# hardware.net
KiCad netlist of a schematic drawn in Altium Designer
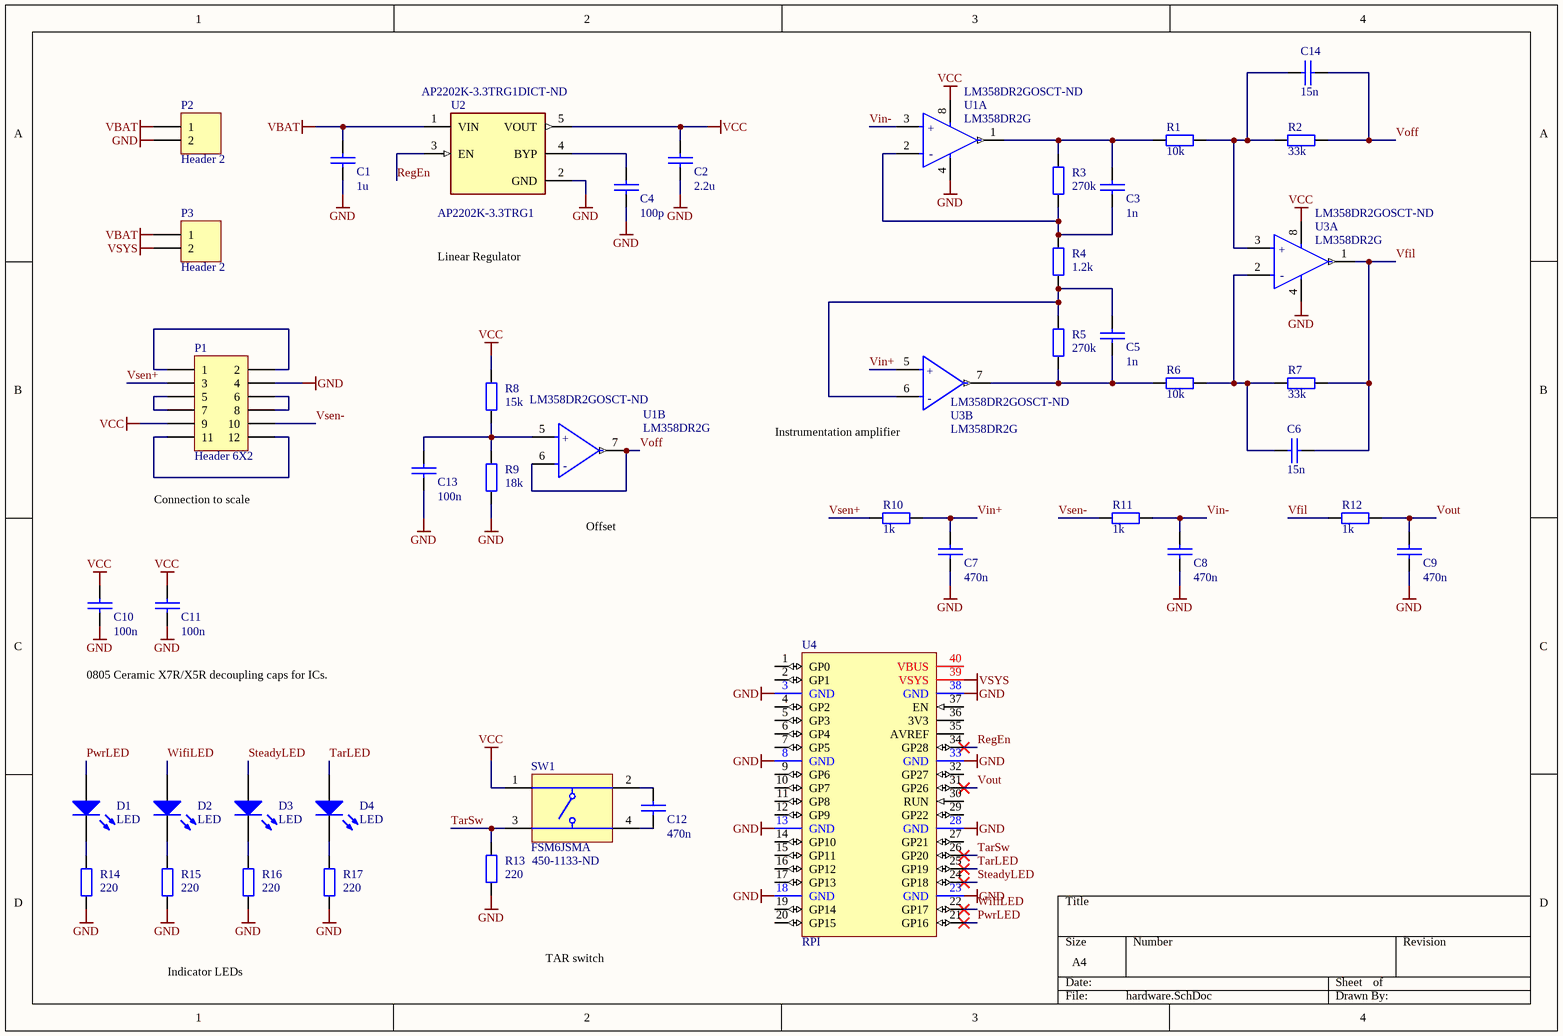
[diagram p0: hardware.SchDoc]

(export (version "E")
  (design (tool "Eeschema 10.0.6"))
  (components
    (comp (ref "C1")
      (value "1u")
      (footprint "EE311_footprints:C0805")
      (description "CCAP0805")
      (libsource (lib "EE311_symbols") (part "CCAP0805"))
    )
    (comp (ref "C2")
      (value "2.2u")
      (footprint "EE311_footprints:C0805")
      (description "CCAP0805")
      (libsource (lib "EE311_symbols") (part "CCAP0805"))
    )
    (comp (ref "C3")
      (value "1n")
      (footprint "EE311_footprints:C0805")
      (description "CCAP0805")
      (libsource (lib "EE311_symbols") (part "CCAP0805"))
    )
    (comp (ref "C4")
      (value "100p")
      (footprint "EE311_footprints:C0805")
      (description "CCAP0805")
      (libsource (lib "EE311_symbols") (part "CCAP0805"))
    )
    (comp (ref "C5")
      (value "1n")
      (footprint "EE311_footprints:C0805")
      (description "CCAP0805")
      (libsource (lib "EE311_symbols") (part "CCAP0805"))
    )
    (comp (ref "C6")
      (value "15n")
      (footprint "EE311_footprints:C0805")
      (description "CCAP0805")
      (libsource (lib "EE311_symbols") (part "CCAP0805"))
    )
    (comp (ref "C7")
      (value "470n")
      (footprint "EE311_footprints:C0805")
      (description "CCAP0805")
      (libsource (lib "EE311_symbols") (part "CCAP0805"))
    )
    (comp (ref "C8")
      (value "470n")
      (footprint "EE311_footprints:C0805")
      (description "CCAP0805")
      (libsource (lib "EE311_symbols") (part "CCAP0805"))
    )
    (comp (ref "C9")
      (value "470n")
      (footprint "EE311_footprints:C0805")
      (description "CCAP0805")
      (libsource (lib "EE311_symbols") (part "CCAP0805"))
    )
    (comp (ref "C10")
      (value "100n")
      (footprint "EE311_footprints:C0805")
      (description "CCAP0805")
      (libsource (lib "EE311_symbols") (part "CCAP0805"))
    )
    (comp (ref "C11")
      (value "100n")
      (footprint "EE311_footprints:C0805")
      (description "CCAP0805")
      (libsource (lib "EE311_symbols") (part "CCAP0805"))
    )
    (comp (ref "C12")
      (value "470n")
      (footprint "EE311_footprints:C0805")
      (description "CCAP0805")
      (libsource (lib "EE311_symbols") (part "CCAP0805"))
    )
    (comp (ref "C13")
      (value "100n")
      (footprint "EE311_footprints:C0805")
      (description "CCAP0805")
      (libsource (lib "EE311_symbols") (part "CCAP0805"))
    )
    (comp (ref "C14")
      (value "15n")
      (footprint "EE311_footprints:C0805")
      (description "CCAP0805")
      (libsource (lib "EE311_symbols") (part "CCAP0805"))
    )
    (comp (ref "D1")
      (value "LED")
      (footprint "EE311_footprints:LED0805")
      (libsource (lib "EE311_symbols") (part "LED"))
    )
    (comp (ref "D2")
      (value "LED")
      (footprint "EE311_footprints:LED0805")
      (libsource (lib "EE311_symbols") (part "LED"))
    )
    (comp (ref "D3")
      (value "LED")
      (footprint "EE311_footprints:LED0805")
      (libsource (lib "EE311_symbols") (part "LED"))
    )
    (comp (ref "D4")
      (value "LED")
      (footprint "EE311_footprints:LED0805")
      (libsource (lib "EE311_symbols") (part "LED"))
    )
    (comp (ref "P1")
      (value "Header 6X2")
      (footprint "HDR2X6")
      (description "Header, 6-Pin, Dual row")
      (fields (field (name "PUBLISHER") "Altium Limited"))
      (libsource (lib "Miscellaneous Connectors") (part "Header 6X2"))
    )
    (comp (ref "P2")
      (value "Header 2")
      (footprint "HDR1X2")
      (description "Header, 2-Pin")
      (fields (field (name "PUBLISHER") "Altium Limited"))
      (libsource (lib "Miscellaneous Connectors") (part "Header 2"))
    )
    (comp (ref "P3")
      (value "Header 2")
      (footprint "HDR1X2")
      (description "Header, 2-Pin")
      (fields (field (name "PUBLISHER") "Altium Limited"))
      (libsource (lib "Miscellaneous Connectors") (part "Header 2"))
    )
    (comp (ref "R1")
      (value "10k")
      (footprint "R0805")
      (description "RES0805")
      (libsource (lib "") (part "RES0805_1"))
    )
    (comp (ref "R2")
      (value "33k")
      (footprint "R0805")
      (description "RES0805")
      (libsource (lib "") (part "RES0805_1"))
    )
    (comp (ref "R3")
      (value "270k")
      (footprint "R0805")
      (description "RES0805")
      (libsource (lib "EE311_symbols") (part "RES0805"))
    )
    (comp (ref "R4")
      (value "1.2k")
      (footprint "R0805")
      (description "RES0805")
      (libsource (lib "EE311_symbols") (part "RES0805"))
    )
    (comp (ref "R5")
      (value "270k")
      (footprint "R0805")
      (description "RES0805")
      (libsource (lib "EE311_symbols") (part "RES0805"))
    )
    (comp (ref "R6")
      (value "10k")
      (footprint "R0805")
      (description "RES0805")
      (libsource (lib "") (part "RES0805_1"))
    )
    (comp (ref "R7")
      (value "33k")
      (footprint "R0805")
      (description "RES0805")
      (libsource (lib "") (part "RES0805_1"))
    )
    (comp (ref "R8")
      (value "15k")
      (footprint "R0805")
      (description "RES0805")
      (libsource (lib "EE311_symbols") (part "RES0805"))
    )
    (comp (ref "R9")
      (value "18k")
      (footprint "R0805")
      (description "RES0805")
      (libsource (lib "EE311_symbols") (part "RES0805"))
    )
    (comp (ref "R10")
      (value "1k")
      (footprint "R0805")
      (description "RES0805")
      (libsource (lib "") (part "RES0805_1"))
    )
    (comp (ref "R11")
      (value "1k")
      (footprint "R0805")
      (description "RES0805")
      (libsource (lib "") (part "RES0805_1"))
    )
    (comp (ref "R12")
      (value "1k")
      (footprint "R0805")
      (description "RES0805")
      (libsource (lib "") (part "RES0805_1"))
    )
    (comp (ref "R13")
      (value "220")
      (footprint "R0805")
      (description "RES0805")
      (libsource (lib "EE311_symbols") (part "RES0805"))
    )
    (comp (ref "R14")
      (value "220")
      (footprint "R0805")
      (description "RES0805")
      (libsource (lib "EE311_symbols") (part "RES0805"))
    )
    (comp (ref "R15")
      (value "220")
      (footprint "R0805")
      (description "RES0805")
      (libsource (lib "EE311_symbols") (part "RES0805"))
    )
    (comp (ref "R16")
      (value "220")
      (footprint "R0805")
      (description "RES0805")
      (libsource (lib "EE311_symbols") (part "RES0805"))
    )
    (comp (ref "R17")
      (value "220")
      (footprint "R0805")
      (description "RES0805")
      (libsource (lib "EE311_symbols") (part "RES0805"))
    )
    (comp (ref "SW1")
      (value "FSM6JSMA")
      (footprint "TECO-FSM6JSMA_V")
      (description "Switch, SPST, 24 V, -35 to 85 degC, 4-Pin SMD, RoHS, Tape and Reel")
      (fields
        (field (name "MANUFACTURER") "TE Connectivity")
        (field (name "SUPPLIER PART NUMBER 1") "450-1133-ND")
      )
      (libsource (lib "Altium Content Vault") (part "SW-SPST-4_A"))
    )
    (comp (ref "U1")
      (value "LM358DR2G")
      (footprint "FP-751-07-IPC_C")
      (description "IC OPAMP GP 2 CIRCUIT 8SOIC")
      (fields
        (field (name "SUPPLIER PART NUMBER 1") "LM358DR2GOSCT-ND")
        (field (name "MANUFACTURER") "ON Semiconductor")
      )
      (libsource (lib "Altium Content Vault") (part "992a6607d1d88c80ee6b45e5ba6cb1b"))
    )
    (comp (ref "U2")
      (value "AP2202K-3.3TRG1")
      (footprint "FP-SOT25-MFG")
      (description "IC REG LINEAR 3.3V 150MA SOT23-5")
      (fields
        (field (name "OCTOPART") "https://octopart.com/ap2202k-3.3trg1-diodes+inc.-30954618")
        (field (name "MANUFACTURER") "Diodes Inc.")
        (field (name "SUPPLIER PART NUMBER 1") "AP2202K-3.3TRG1DICT-ND")
      )
      (libsource (lib "Altium Content Vault") (part "006e7a011770a62fb00db70566099d5"))
    )
    (comp (ref "U3")
      (value "LM358DR2G")
      (footprint "FP-751-07-IPC_C")
      (description "IC OPAMP GP 2 CIRCUIT 8SOIC")
      (fields
        (field (name "SUPPLIER PART NUMBER 1") "LM358DR2GOSCT-ND")
        (field (name "MANUFACTURER") "ON Semiconductor")
      )
      (libsource (lib "Altium Content Vault") (part "992a6607d1d88c80ee6b45e5ba6cb1b"))
    )
    (comp (ref "U4") (value "RPI") (footprint "RPI-PICO-MOD") (libsource (lib "EE311_symbols") (part "RPI")))
  )
  (nets
    (net (code "1") (name "/PwrLED") (class "Default")
      (node (ref "D1") (pin "1") (pinfunction "A_1") (pintype "passive"))
      (node (ref "U4") (pin "21") (pinfunction "GP16_21") (pintype "bidirectional"))
    )
    (net (code "2") (name "/RegEn") (class "Default")
      (node (ref "U2") (pin "3") (pinfunction "EN_3") (pintype "input"))
      (node (ref "U4") (pin "34") (pinfunction "GP28_34") (pintype "bidirectional"))
    )
    (net (code "3") (name "/SteadyLED") (class "Default")
      (node (ref "D3") (pin "1") (pinfunction "A_1") (pintype "passive"))
      (node (ref "U4") (pin "24") (pinfunction "GP18_24") (pintype "bidirectional"))
    )
    (net (code "4") (name "/TarLED") (class "Default")
      (node (ref "D4") (pin "1") (pinfunction "A_1") (pintype "passive"))
      (node (ref "U4") (pin "25") (pinfunction "GP19_25") (pintype "bidirectional"))
    )
    (net (code "5") (name "/TarSw") (class "Default")
      (node (ref "R13") (pin "2") (pinfunction "2_2") (pintype "passive"))
      (node (ref "SW1") (pin "3") (pinfunction "3_3") (pintype "passive"))
      (node (ref "U4") (pin "26") (pinfunction "GP20_26") (pintype "bidirectional"))
    )
    (net (code "6") (name "/Vfil") (class "Default")
      (node (ref "C6") (pin "1") (pinfunction "1_1") (pintype "passive"))
      (node (ref "R12") (pin "2") (pinfunction "2_2") (pintype "passive"))
      (node (ref "R7") (pin "1") (pinfunction "1_1") (pintype "passive"))
      (node (ref "U3") (pin "1") (pinfunction "OUTPUT_A_1") (pintype "output"))
    )
    (net (code "7") (name "/Vin+") (class "Default")
      (node (ref "C7") (pin "2") (pinfunction "2_2") (pintype "passive"))
      (node (ref "R10") (pin "1") (pinfunction "1_1") (pintype "passive"))
      (node (ref "U3") (pin "5") (pinfunction "INPUT_B+_5") (pintype "tri_state"))
    )
    (net (code "8") (name "/Vin-") (class "Default")
      (node (ref "C8") (pin "2") (pinfunction "2_2") (pintype "passive"))
      (node (ref "R11") (pin "1") (pinfunction "1_1") (pintype "passive"))
      (node (ref "U1") (pin "3") (pinfunction "INPUT_A+_3") (pintype "tri_state"))
    )
    (net (code "9") (name "/Voff") (class "Default")
      (node (ref "C14") (pin "1") (pinfunction "1_1") (pintype "passive"))
      (node (ref "R2") (pin "1") (pinfunction "1_1") (pintype "passive"))
      (node (ref "U1") (pin "6") (pinfunction "INPUT_B-_6") (pintype "tri_state"))
      (node (ref "U1") (pin "7") (pinfunction "OUTPUT_B_7") (pintype "output"))
    )
    (net (code "10") (name "/Vout") (class "Default")
      (node (ref "C9") (pin "2") (pinfunction "2_2") (pintype "passive"))
      (node (ref "R12") (pin "1") (pinfunction "1_1") (pintype "passive"))
      (node (ref "U4") (pin "31") (pinfunction "GP26_31") (pintype "bidirectional"))
    )
    (net (code "11") (name "/Vsen+") (class "Default")
      (node (ref "P1") (pin "3") (pinfunction "3_3") (pintype "passive"))
      (node (ref "R10") (pin "2") (pinfunction "2_2") (pintype "passive"))
    )
    (net (code "12") (name "/Vsen-") (class "Default")
      (node (ref "P1") (pin "10") (pinfunction "10_10") (pintype "passive"))
      (node (ref "R11") (pin "2") (pinfunction "2_2") (pintype "passive"))
    )
    (net (code "13") (name "/WifiLED") (class "Default")
      (node (ref "D2") (pin "1") (pinfunction "A_1") (pintype "passive"))
      (node (ref "U4") (pin "22") (pinfunction "GP17_22") (pintype "bidirectional"))
    )
    (net (code "14") (name "GND") (class "Default")
      (node (ref "C1") (pin "1") (pinfunction "1_1") (pintype "passive"))
      (node (ref "C10") (pin "1") (pinfunction "1_1") (pintype "passive"))
      (node (ref "C11") (pin "1") (pinfunction "1_1") (pintype "passive"))
      (node (ref "C13") (pin "1") (pinfunction "1_1") (pintype "passive"))
      (node (ref "C2") (pin "1") (pinfunction "1_1") (pintype "passive"))
      (node (ref "C4") (pin "1") (pinfunction "1_1") (pintype "passive"))
      (node (ref "C7") (pin "1") (pinfunction "1_1") (pintype "passive"))
      (node (ref "C8") (pin "1") (pinfunction "1_1") (pintype "passive"))
      (node (ref "C9") (pin "1") (pinfunction "1_1") (pintype "passive"))
      (node (ref "P1") (pin "4") (pinfunction "4_4") (pintype "passive"))
      (node (ref "P2") (pin "2") (pinfunction "2_2") (pintype "passive"))
      (node (ref "R13") (pin "1") (pinfunction "1_1") (pintype "passive"))
      (node (ref "R14") (pin "1") (pinfunction "1_1") (pintype "passive"))
      (node (ref "R15") (pin "1") (pinfunction "1_1") (pintype "passive"))
      (node (ref "R16") (pin "1") (pinfunction "1_1") (pintype "passive"))
      (node (ref "R17") (pin "1") (pinfunction "1_1") (pintype "passive"))
      (node (ref "R9") (pin "1") (pinfunction "1_1") (pintype "passive"))
      (node (ref "U1") (pin "4") (pinfunction "VEE/GND_4") (pintype "power_in"))
      (node (ref "U2") (pin "2") (pinfunction "GND_2") (pintype "power_in"))
      (node (ref "U3") (pin "4") (pinfunction "VEE/GND_4") (pintype "power_in"))
      (node (ref "U4") (pin "13") (pinfunction "GND_13") (pintype "power_in"))
      (node (ref "U4") (pin "18") (pinfunction "GND_18") (pintype "power_in"))
      (node (ref "U4") (pin "23") (pinfunction "GND_23") (pintype "power_in"))
      (node (ref "U4") (pin "28") (pinfunction "GND_28") (pintype "power_in"))
      (node (ref "U4") (pin "3") (pinfunction "GND_3") (pintype "power_in"))
      (node (ref "U4") (pin "33") (pinfunction "GND_33") (pintype "power_in"))
      (node (ref "U4") (pin "38") (pinfunction "GND_38") (pintype "power_in"))
      (node (ref "U4") (pin "8") (pinfunction "GND_8") (pintype "power_in"))
    )
    (net (code "15") (name "Net-(C12-Pad1)") (class "Default")
      (node (ref "C12") (pin "1") (pinfunction "1_1") (pintype "passive"))
      (node (ref "SW1") (pin "4") (pinfunction "4_4") (pintype "passive"))
    )
    (net (code "16") (name "Net-(C12-Pad2)") (class "Default")
      (node (ref "C12") (pin "2") (pinfunction "2_2") (pintype "passive"))
      (node (ref "SW1") (pin "2") (pinfunction "2_2") (pintype "passive"))
    )
    (net (code "17") (name "Net-(D1-K)") (class "Default")
      (node (ref "D1") (pin "2") (pinfunction "K_2") (pintype "passive"))
      (node (ref "R14") (pin "2") (pinfunction "2_2") (pintype "passive"))
    )
    (net (code "18") (name "Net-(D2-K)") (class "Default")
      (node (ref "D2") (pin "2") (pinfunction "K_2") (pintype "passive"))
      (node (ref "R15") (pin "2") (pinfunction "2_2") (pintype "passive"))
    )
    (net (code "19") (name "Net-(D3-K)") (class "Default")
      (node (ref "D3") (pin "2") (pinfunction "K_2") (pintype "passive"))
      (node (ref "R16") (pin "2") (pinfunction "2_2") (pintype "passive"))
    )
    (net (code "20") (name "Net-(D4-K)") (class "Default")
      (node (ref "D4") (pin "2") (pinfunction "K_2") (pintype "passive"))
      (node (ref "R17") (pin "2") (pinfunction "2_2") (pintype "passive"))
    )
    (net (code "21") (name "Net-(P1-Pad1)") (class "Default")
      (node (ref "P1") (pin "1") (pinfunction "1_1") (pintype "passive"))
      (node (ref "P1") (pin "2") (pinfunction "2_2") (pintype "passive"))
    )
    (net (code "22") (name "Net-(P1-Pad5)") (class "Default")
      (node (ref "P1") (pin "5") (pinfunction "5_5") (pintype "passive"))
      (node (ref "P1") (pin "7") (pinfunction "7_7") (pintype "passive"))
    )
    (net (code "23") (name "Net-(P1-Pad6)") (class "Default")
      (node (ref "P1") (pin "6") (pinfunction "6_6") (pintype "passive"))
      (node (ref "P1") (pin "8") (pinfunction "8_8") (pintype "passive"))
    )
    (net (code "24") (name "Net-(P1-Pad11)") (class "Default")
      (node (ref "P1") (pin "11") (pinfunction "11_11") (pintype "passive"))
      (node (ref "P1") (pin "12") (pinfunction "12_12") (pintype "passive"))
    )
    (net (code "25") (name "Net-(U1A-INPUT_A-)") (class "Default")
      (node (ref "C3") (pin "1") (pinfunction "1_1") (pintype "passive"))
      (node (ref "R3") (pin "1") (pinfunction "1_1") (pintype "passive"))
      (node (ref "R4") (pin "2") (pinfunction "2_2") (pintype "passive"))
      (node (ref "U1") (pin "2") (pinfunction "INPUT_A-_2") (pintype "tri_state"))
    )
    (net (code "26") (name "Net-(U1A-OUTPUT_A)") (class "Default")
      (node (ref "C3") (pin "2") (pinfunction "2_2") (pintype "passive"))
      (node (ref "R1") (pin "2") (pinfunction "2_2") (pintype "passive"))
      (node (ref "R3") (pin "2") (pinfunction "2_2") (pintype "passive"))
      (node (ref "U1") (pin "1") (pinfunction "OUTPUT_A_1") (pintype "output"))
    )
    (net (code "27") (name "Net-(U1B-INPUT_B+)") (class "Default")
      (node (ref "C13") (pin "2") (pinfunction "2_2") (pintype "passive"))
      (node (ref "R8") (pin "1") (pinfunction "1_1") (pintype "passive"))
      (node (ref "R9") (pin "2") (pinfunction "2_2") (pintype "passive"))
      (node (ref "U1") (pin "5") (pinfunction "INPUT_B+_5") (pintype "tri_state"))
    )
    (net (code "28") (name "Net-(U2-BYP)") (class "Default")
      (node (ref "C4") (pin "2") (pinfunction "2_2") (pintype "passive"))
      (node (ref "U2") (pin "4") (pinfunction "BYP_4") (pintype "passive"))
    )
    (net (code "29") (name "Net-(U3A-INPUT_A+)") (class "Default")
      (node (ref "C14") (pin "2") (pinfunction "2_2") (pintype "passive"))
      (node (ref "R1") (pin "1") (pinfunction "1_1") (pintype "passive"))
      (node (ref "R2") (pin "2") (pinfunction "2_2") (pintype "passive"))
      (node (ref "U3") (pin "3") (pinfunction "INPUT_A+_3") (pintype "tri_state"))
    )
    (net (code "30") (name "Net-(U3A-INPUT_A-)") (class "Default")
      (node (ref "C6") (pin "2") (pinfunction "2_2") (pintype "passive"))
      (node (ref "R6") (pin "1") (pinfunction "1_1") (pintype "passive"))
      (node (ref "R7") (pin "2") (pinfunction "2_2") (pintype "passive"))
      (node (ref "U3") (pin "2") (pinfunction "INPUT_A-_2") (pintype "tri_state"))
    )
    (net (code "31") (name "Net-(U3B-INPUT_B-)") (class "Default")
      (node (ref "C5") (pin "2") (pinfunction "2_2") (pintype "passive"))
      (node (ref "R4") (pin "1") (pinfunction "1_1") (pintype "passive"))
      (node (ref "R5") (pin "2") (pinfunction "2_2") (pintype "passive"))
      (node (ref "U3") (pin "6") (pinfunction "INPUT_B-_6") (pintype "tri_state"))
    )
    (net (code "32") (name "Net-(U3B-OUTPUT_B)") (class "Default")
      (node (ref "C5") (pin "1") (pinfunction "1_1") (pintype "passive"))
      (node (ref "R5") (pin "1") (pinfunction "1_1") (pintype "passive"))
      (node (ref "R6") (pin "2") (pinfunction "2_2") (pintype "passive"))
      (node (ref "U3") (pin "7") (pinfunction "OUTPUT_B_7") (pintype "output"))
    )
    (net (code "33") (name "VBAT") (class "Default")
      (node (ref "C1") (pin "2") (pinfunction "2_2") (pintype "passive"))
      (node (ref "P2") (pin "1") (pinfunction "1_1") (pintype "passive"))
      (node (ref "P3") (pin "1") (pinfunction "1_1") (pintype "passive"))
      (node (ref "U2") (pin "1") (pinfunction "VIN_1") (pintype "power_in"))
    )
    (net (code "34") (name "VCC") (class "Default")
      (node (ref "C10") (pin "2") (pinfunction "2_2") (pintype "passive"))
      (node (ref "C11") (pin "2") (pinfunction "2_2") (pintype "passive"))
      (node (ref "C2") (pin "2") (pinfunction "2_2") (pintype "passive"))
      (node (ref "P1") (pin "9") (pinfunction "9_9") (pintype "passive"))
      (node (ref "R8") (pin "2") (pinfunction "2_2") (pintype "passive"))
      (node (ref "SW1") (pin "1") (pinfunction "1_1") (pintype "passive"))
      (node (ref "U1") (pin "8") (pinfunction "VCC_8") (pintype "power_in"))
      (node (ref "U2") (pin "5") (pinfunction "VOUT_5") (pintype "output"))
      (node (ref "U3") (pin "8") (pinfunction "VCC_8") (pintype "power_in"))
    )
    (net (code "35") (name "VSYS") (class "Default")
      (node (ref "P3") (pin "2") (pinfunction "2_2") (pintype "passive"))
      (node (ref "U4") (pin "39") (pinfunction "VSYS_39") (pintype "power_in"))
    )
    (net (code "36") (name "unconnected-(U4-3V3-Pad36)") (class "Default")
      (node (ref "U4") (pin "36") (pinfunction "3V3_36") (pintype "power_in"))
    )
    (net (code "37") (name "unconnected-(U4-AVREF-Pad35)") (class "Default")
      (node (ref "U4") (pin "35") (pinfunction "AVREF_35") (pintype "power_in"))
    )
    (net (code "38") (name "unconnected-(U4-EN-Pad37)") (class "Default")
      (node (ref "U4") (pin "37") (pinfunction "EN_37") (pintype "input"))
    )
    (net (code "39") (name "unconnected-(U4-GP0-Pad1)") (class "Default")
      (node (ref "U4") (pin "1") (pinfunction "GP0_1") (pintype "bidirectional"))
    )
    (net (code "40") (name "unconnected-(U4-GP1-Pad2)") (class "Default")
      (node (ref "U4") (pin "2") (pinfunction "GP1_2") (pintype "bidirectional"))
    )
    (net (code "41") (name "unconnected-(U4-GP2-Pad4)") (class "Default")
      (node (ref "U4") (pin "4") (pinfunction "GP2_4") (pintype "bidirectional"))
    )
    (net (code "42") (name "unconnected-(U4-GP3-Pad5)") (class "Default")
      (node (ref "U4") (pin "5") (pinfunction "GP3_5") (pintype "bidirectional"))
    )
    (net (code "43") (name "unconnected-(U4-GP4-Pad6)") (class "Default")
      (node (ref "U4") (pin "6") (pinfunction "GP4_6") (pintype "bidirectional"))
    )
    (net (code "44") (name "unconnected-(U4-GP5-Pad7)") (class "Default")
      (node (ref "U4") (pin "7") (pinfunction "GP5_7") (pintype "bidirectional"))
    )
    (net (code "45") (name "unconnected-(U4-GP6-Pad9)") (class "Default")
      (node (ref "U4") (pin "9") (pinfunction "GP6_9") (pintype "bidirectional"))
    )
    (net (code "46") (name "unconnected-(U4-GP7-Pad10)") (class "Default")
      (node (ref "U4") (pin "10") (pinfunction "GP7_10") (pintype "bidirectional"))
    )
    (net (code "47") (name "unconnected-(U4-GP8-Pad11)") (class "Default")
      (node (ref "U4") (pin "11") (pinfunction "GP8_11") (pintype "bidirectional"))
    )
    (net (code "48") (name "unconnected-(U4-GP9-Pad12)") (class "Default")
      (node (ref "U4") (pin "12") (pinfunction "GP9_12") (pintype "bidirectional"))
    )
    (net (code "49") (name "unconnected-(U4-GP10-Pad14)") (class "Default")
      (node (ref "U4") (pin "14") (pinfunction "GP10_14") (pintype "bidirectional"))
    )
    (net (code "50") (name "unconnected-(U4-GP11-Pad15)") (class "Default")
      (node (ref "U4") (pin "15") (pinfunction "GP11_15") (pintype "bidirectional"))
    )
    (net (code "51") (name "unconnected-(U4-GP12-Pad16)") (class "Default")
      (node (ref "U4") (pin "16") (pinfunction "GP12_16") (pintype "bidirectional"))
    )
    (net (code "52") (name "unconnected-(U4-GP13-Pad17)") (class "Default")
      (node (ref "U4") (pin "17") (pinfunction "GP13_17") (pintype "bidirectional"))
    )
    (net (code "53") (name "unconnected-(U4-GP14-Pad19)") (class "Default")
      (node (ref "U4") (pin "19") (pinfunction "GP14_19") (pintype "bidirectional"))
    )
    (net (code "54") (name "unconnected-(U4-GP15-Pad20)") (class "Default")
      (node (ref "U4") (pin "20") (pinfunction "GP15_20") (pintype "bidirectional"))
    )
    (net (code "55") (name "unconnected-(U4-GP21-Pad27)") (class "Default")
      (node (ref "U4") (pin "27") (pinfunction "GP21_27") (pintype "bidirectional"))
    )
    (net (code "56") (name "unconnected-(U4-GP22-Pad29)") (class "Default")
      (node (ref "U4") (pin "29") (pinfunction "GP22_29") (pintype "bidirectional"))
    )
    (net (code "57") (name "unconnected-(U4-GP27-Pad32)") (class "Default")
      (node (ref "U4") (pin "32") (pinfunction "GP27_32") (pintype "bidirectional"))
    )
    (net (code "58") (name "unconnected-(U4-RUN-Pad30)") (class "Default")
      (node (ref "U4") (pin "30") (pinfunction "RUN_30") (pintype "input"))
    )
    (net (code "59") (name "unconnected-(U4-VBUS-Pad40)") (class "Default")
      (node (ref "U4") (pin "40") (pinfunction "VBUS_40") (pintype "power_in"))
    )
  )
)
